# Logic_adapter.net
KiCad netlist of a schematic drawn in Altium Designer
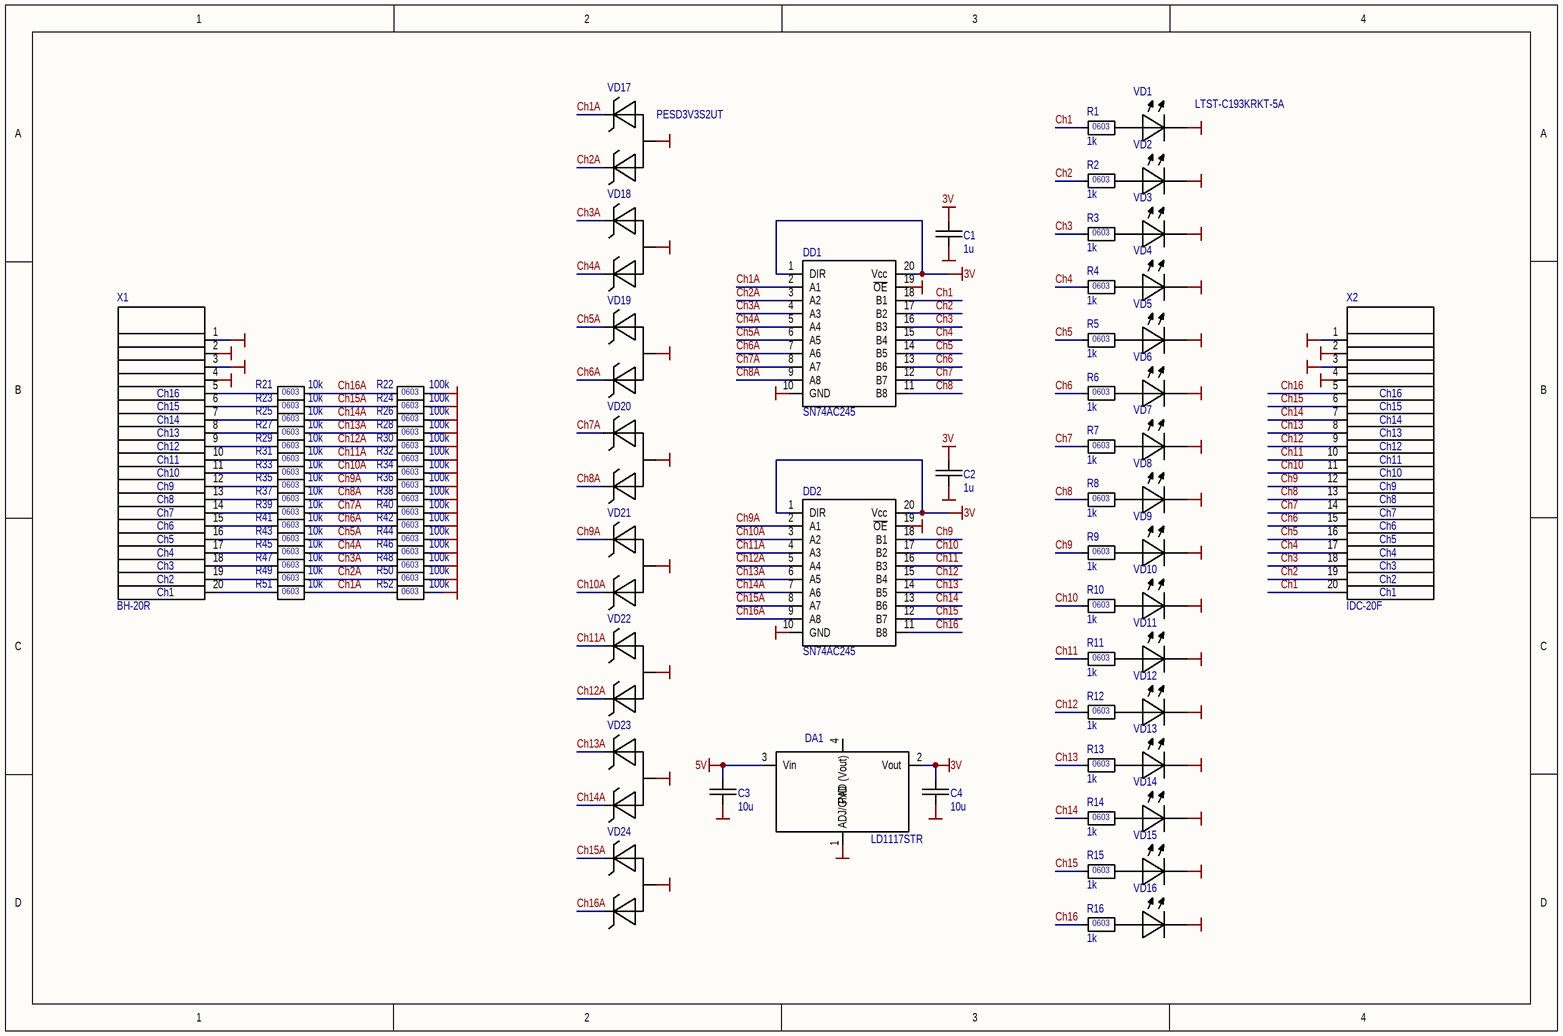
[diagram p0: Logic adapter.SchDoc]

(export (version "E")
  (design (tool "Eeschema 10.0.6"))
  (components
    (comp (ref "C1")
      (value "1u")
      (footprint "C0603")
      (description "General  ceramic capacitor")
      (fields (field (name "PART NUMBER") "GRM185C81A105ME36#") (field (name "VOLTAGE") "10V"))
      (libsource (lib "altium") (part "Capacitor"))
    )
    (comp (ref "C2")
      (value "1u")
      (footprint "C0603")
      (description "General  ceramic capacitor")
      (fields (field (name "PART NUMBER") "GRM185C81A105ME36#") (field (name "VOLTAGE") "10V"))
      (libsource (lib "altium") (part "Capacitor"))
    )
    (comp (ref "C3")
      (value "10u")
      (footprint "C0805")
      (description "General  ceramic capacitor")
      (fields
        (field (name "PART NUMBER") "GRM21BC81A106KE18#")
        (field (name "ALT PART") "C2012X6S1A106K085AC(TDK)")
      )
      (libsource (lib "altium") (part "Capacitor"))
    )
    (comp (ref "C4")
      (value "10u")
      (footprint "C0805")
      (description "General  ceramic capacitor")
      (fields
        (field (name "PART NUMBER") "GRM21BC81A106KE18#")
        (field (name "ALT PART") "C2012X6S1A106K085AC(TDK)")
      )
      (libsource (lib "altium") (part "Capacitor"))
    )
    (comp (ref "DA1")
      (value "~")
      (footprint "ON SEMI SOT-223 ST(318H)")
      (description "LDO ADJ 0.8mA")
      (fields (field (name "PART NUMBER") "LD1117STR") (field (name "LCSC PART #") "C426566"))
      (libsource (lib "altium") (part "LD1117STR"))
    )
    (comp (ref "DD1")
      (value "SN74AC245")
      (footprint "TI-SOIC20 DW")
      (description "Octal bus transceiver")
      (fields (field (name "PART NUMBER") "SN74AC245DW") (field (name "LCSC PART #") "C354145"))
      (libsource (lib "altium") (part "SN74AC245"))
    )
    (comp (ref "DD2")
      (value "SN74AC245")
      (footprint "TI-SOIC20 DW")
      (description "Octal bus transceiver")
      (fields (field (name "PART NUMBER") "SN74AC245DW") (field (name "LCSC PART #") "C354145"))
      (libsource (lib "altium") (part "SN74AC245"))
    )
    (comp (ref "R1")
      (value "1k")
      (footprint "R0603")
      (description "Thick Film Chip Resistor - CR Series")
      (fields (field (name "PART NUMBER") "CR-03FL7----1k") (field (name "ALT PART") "RTT031001FTH (Ralec)"))
      (libsource (lib "altium") (part "Resistor - 0603"))
    )
    (comp (ref "R2")
      (value "1k")
      (footprint "R0603")
      (description "Thick Film Chip Resistor - CR Series")
      (fields (field (name "PART NUMBER") "CR-03FL7----1k") (field (name "ALT PART") "RTT031001FTH (Ralec)"))
      (libsource (lib "altium") (part "Resistor - 0603"))
    )
    (comp (ref "R3")
      (value "1k")
      (footprint "R0603")
      (description "Thick Film Chip Resistor - CR Series")
      (fields (field (name "PART NUMBER") "CR-03FL7----1k") (field (name "ALT PART") "RTT031001FTH (Ralec)"))
      (libsource (lib "altium") (part "Resistor - 0603"))
    )
    (comp (ref "R4")
      (value "1k")
      (footprint "R0603")
      (description "Thick Film Chip Resistor - CR Series")
      (fields (field (name "PART NUMBER") "CR-03FL7----1k") (field (name "ALT PART") "RTT031001FTH (Ralec)"))
      (libsource (lib "altium") (part "Resistor - 0603"))
    )
    (comp (ref "R5")
      (value "1k")
      (footprint "R0603")
      (description "Thick Film Chip Resistor - CR Series")
      (fields (field (name "PART NUMBER") "CR-03FL7----1k") (field (name "ALT PART") "RTT031001FTH (Ralec)"))
      (libsource (lib "altium") (part "Resistor - 0603"))
    )
    (comp (ref "R6")
      (value "1k")
      (footprint "R0603")
      (description "Thick Film Chip Resistor - CR Series")
      (fields (field (name "PART NUMBER") "CR-03FL7----1k") (field (name "ALT PART") "RTT031001FTH (Ralec)"))
      (libsource (lib "altium") (part "Resistor - 0603"))
    )
    (comp (ref "R7")
      (value "1k")
      (footprint "R0603")
      (description "Thick Film Chip Resistor - CR Series")
      (fields (field (name "PART NUMBER") "CR-03FL7----1k") (field (name "ALT PART") "RTT031001FTH (Ralec)"))
      (libsource (lib "altium") (part "Resistor - 0603"))
    )
    (comp (ref "R8")
      (value "1k")
      (footprint "R0603")
      (description "Thick Film Chip Resistor - CR Series")
      (fields (field (name "PART NUMBER") "CR-03FL7----1k") (field (name "ALT PART") "RTT031001FTH (Ralec)"))
      (libsource (lib "altium") (part "Resistor - 0603"))
    )
    (comp (ref "R9")
      (value "1k")
      (footprint "R0603")
      (description "Thick Film Chip Resistor - CR Series")
      (fields (field (name "PART NUMBER") "CR-03FL7----1k") (field (name "ALT PART") "RTT031001FTH (Ralec)"))
      (libsource (lib "altium") (part "Resistor - 0603"))
    )
    (comp (ref "R10")
      (value "1k")
      (footprint "R0603")
      (description "Thick Film Chip Resistor - CR Series")
      (fields (field (name "PART NUMBER") "CR-03FL7----1k") (field (name "ALT PART") "RTT031001FTH (Ralec)"))
      (libsource (lib "altium") (part "Resistor - 0603"))
    )
    (comp (ref "R11")
      (value "1k")
      (footprint "R0603")
      (description "Thick Film Chip Resistor - CR Series")
      (fields (field (name "PART NUMBER") "CR-03FL7----1k") (field (name "ALT PART") "RTT031001FTH (Ralec)"))
      (libsource (lib "altium") (part "Resistor - 0603"))
    )
    (comp (ref "R12")
      (value "1k")
      (footprint "R0603")
      (description "Thick Film Chip Resistor - CR Series")
      (fields (field (name "PART NUMBER") "CR-03FL7----1k") (field (name "ALT PART") "RTT031001FTH (Ralec)"))
      (libsource (lib "altium") (part "Resistor - 0603"))
    )
    (comp (ref "R13")
      (value "1k")
      (footprint "R0603")
      (description "Thick Film Chip Resistor - CR Series")
      (fields (field (name "PART NUMBER") "CR-03FL7----1k") (field (name "ALT PART") "RTT031001FTH (Ralec)"))
      (libsource (lib "altium") (part "Resistor - 0603"))
    )
    (comp (ref "R14")
      (value "1k")
      (footprint "R0603")
      (description "Thick Film Chip Resistor - CR Series")
      (fields (field (name "PART NUMBER") "CR-03FL7----1k") (field (name "ALT PART") "RTT031001FTH (Ralec)"))
      (libsource (lib "altium") (part "Resistor - 0603"))
    )
    (comp (ref "R15")
      (value "1k")
      (footprint "R0603")
      (description "Thick Film Chip Resistor - CR Series")
      (fields (field (name "PART NUMBER") "CR-03FL7----1k") (field (name "ALT PART") "RTT031001FTH (Ralec)"))
      (libsource (lib "altium") (part "Resistor - 0603"))
    )
    (comp (ref "R16")
      (value "1k")
      (footprint "R0603")
      (description "Thick Film Chip Resistor - CR Series")
      (fields (field (name "PART NUMBER") "CR-03FL7----1k") (field (name "ALT PART") "RTT031001FTH (Ralec)"))
      (libsource (lib "altium") (part "Resistor - 0603"))
    )
    (comp (ref "R21")
      (value "10k")
      (footprint "R0603")
      (description "Thick Film Chip Resistor - CR Series")
      (fields (field (name "PART NUMBER") "CR-03FL7---10k") (field (name "ALT PART") "RTT031002FTH (Ralec)"))
      (libsource (lib "altium") (part "Resistor - 0603"))
    )
    (comp (ref "R22")
      (value "100k")
      (footprint "R0603")
      (description "Thick Film Chip Resistor - CR Series")
      (fields (field (name "PART NUMBER") "CR-03FL7--100k") (field (name "ALT PART") "RTT031003FTH (Ralec)"))
      (libsource (lib "altium") (part "Resistor - 0603"))
    )
    (comp (ref "R23")
      (value "10k")
      (footprint "R0603")
      (description "Thick Film Chip Resistor - CR Series")
      (fields (field (name "PART NUMBER") "CR-03FL7---10k") (field (name "ALT PART") "RTT031002FTH (Ralec)"))
      (libsource (lib "altium") (part "Resistor - 0603"))
    )
    (comp (ref "R24")
      (value "100k")
      (footprint "R0603")
      (description "Thick Film Chip Resistor - CR Series")
      (fields (field (name "PART NUMBER") "CR-03FL7--100k") (field (name "ALT PART") "RTT031003FTH (Ralec)"))
      (libsource (lib "altium") (part "Resistor - 0603"))
    )
    (comp (ref "R25")
      (value "10k")
      (footprint "R0603")
      (description "Thick Film Chip Resistor - CR Series")
      (fields (field (name "PART NUMBER") "CR-03FL7---10k") (field (name "ALT PART") "RTT031002FTH (Ralec)"))
      (libsource (lib "altium") (part "Resistor - 0603"))
    )
    (comp (ref "R26")
      (value "100k")
      (footprint "R0603")
      (description "Thick Film Chip Resistor - CR Series")
      (fields (field (name "PART NUMBER") "CR-03FL7--100k") (field (name "ALT PART") "RTT031003FTH (Ralec)"))
      (libsource (lib "altium") (part "Resistor - 0603"))
    )
    (comp (ref "R27")
      (value "10k")
      (footprint "R0603")
      (description "Thick Film Chip Resistor - CR Series")
      (fields (field (name "PART NUMBER") "CR-03FL7---10k") (field (name "ALT PART") "RTT031002FTH (Ralec)"))
      (libsource (lib "altium") (part "Resistor - 0603"))
    )
    (comp (ref "R28")
      (value "100k")
      (footprint "R0603")
      (description "Thick Film Chip Resistor - CR Series")
      (fields (field (name "PART NUMBER") "CR-03FL7--100k") (field (name "ALT PART") "RTT031003FTH (Ralec)"))
      (libsource (lib "altium") (part "Resistor - 0603"))
    )
    (comp (ref "R29")
      (value "10k")
      (footprint "R0603")
      (description "Thick Film Chip Resistor - CR Series")
      (fields (field (name "PART NUMBER") "CR-03FL7---10k") (field (name "ALT PART") "RTT031002FTH (Ralec)"))
      (libsource (lib "altium") (part "Resistor - 0603"))
    )
    (comp (ref "R30")
      (value "100k")
      (footprint "R0603")
      (description "Thick Film Chip Resistor - CR Series")
      (fields (field (name "PART NUMBER") "CR-03FL7--100k") (field (name "ALT PART") "RTT031003FTH (Ralec)"))
      (libsource (lib "altium") (part "Resistor - 0603"))
    )
    (comp (ref "R31")
      (value "10k")
      (footprint "R0603")
      (description "Thick Film Chip Resistor - CR Series")
      (fields (field (name "PART NUMBER") "CR-03FL7---10k") (field (name "ALT PART") "RTT031002FTH (Ralec)"))
      (libsource (lib "altium") (part "Resistor - 0603"))
    )
    (comp (ref "R32")
      (value "100k")
      (footprint "R0603")
      (description "Thick Film Chip Resistor - CR Series")
      (fields (field (name "PART NUMBER") "CR-03FL7--100k") (field (name "ALT PART") "RTT031003FTH (Ralec)"))
      (libsource (lib "altium") (part "Resistor - 0603"))
    )
    (comp (ref "R33")
      (value "10k")
      (footprint "R0603")
      (description "Thick Film Chip Resistor - CR Series")
      (fields (field (name "PART NUMBER") "CR-03FL7---10k") (field (name "ALT PART") "RTT031002FTH (Ralec)"))
      (libsource (lib "altium") (part "Resistor - 0603"))
    )
    (comp (ref "R34")
      (value "100k")
      (footprint "R0603")
      (description "Thick Film Chip Resistor - CR Series")
      (fields (field (name "PART NUMBER") "CR-03FL7--100k") (field (name "ALT PART") "RTT031003FTH (Ralec)"))
      (libsource (lib "altium") (part "Resistor - 0603"))
    )
    (comp (ref "R35")
      (value "10k")
      (footprint "R0603")
      (description "Thick Film Chip Resistor - CR Series")
      (fields (field (name "PART NUMBER") "CR-03FL7---10k") (field (name "ALT PART") "RTT031002FTH (Ralec)"))
      (libsource (lib "altium") (part "Resistor - 0603"))
    )
    (comp (ref "R36")
      (value "100k")
      (footprint "R0603")
      (description "Thick Film Chip Resistor - CR Series")
      (fields (field (name "PART NUMBER") "CR-03FL7--100k") (field (name "ALT PART") "RTT031003FTH (Ralec)"))
      (libsource (lib "altium") (part "Resistor - 0603"))
    )
    (comp (ref "R37")
      (value "10k")
      (footprint "R0603")
      (description "Thick Film Chip Resistor - CR Series")
      (fields (field (name "PART NUMBER") "CR-03FL7---10k") (field (name "ALT PART") "RTT031002FTH (Ralec)"))
      (libsource (lib "altium") (part "Resistor - 0603"))
    )
    (comp (ref "R38")
      (value "100k")
      (footprint "R0603")
      (description "Thick Film Chip Resistor - CR Series")
      (fields (field (name "PART NUMBER") "CR-03FL7--100k") (field (name "ALT PART") "RTT031003FTH (Ralec)"))
      (libsource (lib "altium") (part "Resistor - 0603"))
    )
    (comp (ref "R39")
      (value "10k")
      (footprint "R0603")
      (description "Thick Film Chip Resistor - CR Series")
      (fields (field (name "PART NUMBER") "CR-03FL7---10k") (field (name "ALT PART") "RTT031002FTH (Ralec)"))
      (libsource (lib "altium") (part "Resistor - 0603"))
    )
    (comp (ref "R40")
      (value "100k")
      (footprint "R0603")
      (description "Thick Film Chip Resistor - CR Series")
      (fields (field (name "PART NUMBER") "CR-03FL7--100k") (field (name "ALT PART") "RTT031003FTH (Ralec)"))
      (libsource (lib "altium") (part "Resistor - 0603"))
    )
    (comp (ref "R41")
      (value "10k")
      (footprint "R0603")
      (description "Thick Film Chip Resistor - CR Series")
      (fields (field (name "PART NUMBER") "CR-03FL7---10k") (field (name "ALT PART") "RTT031002FTH (Ralec)"))
      (libsource (lib "altium") (part "Resistor - 0603"))
    )
    (comp (ref "R42")
      (value "100k")
      (footprint "R0603")
      (description "Thick Film Chip Resistor - CR Series")
      (fields (field (name "PART NUMBER") "CR-03FL7--100k") (field (name "ALT PART") "RTT031003FTH (Ralec)"))
      (libsource (lib "altium") (part "Resistor - 0603"))
    )
    (comp (ref "R43")
      (value "10k")
      (footprint "R0603")
      (description "Thick Film Chip Resistor - CR Series")
      (fields (field (name "PART NUMBER") "CR-03FL7---10k") (field (name "ALT PART") "RTT031002FTH (Ralec)"))
      (libsource (lib "altium") (part "Resistor - 0603"))
    )
    (comp (ref "R44")
      (value "100k")
      (footprint "R0603")
      (description "Thick Film Chip Resistor - CR Series")
      (fields (field (name "PART NUMBER") "CR-03FL7--100k") (field (name "ALT PART") "RTT031003FTH (Ralec)"))
      (libsource (lib "altium") (part "Resistor - 0603"))
    )
    (comp (ref "R45")
      (value "10k")
      (footprint "R0603")
      (description "Thick Film Chip Resistor - CR Series")
      (fields (field (name "PART NUMBER") "CR-03FL7---10k") (field (name "ALT PART") "RTT031002FTH (Ralec)"))
      (libsource (lib "altium") (part "Resistor - 0603"))
    )
    (comp (ref "R46")
      (value "100k")
      (footprint "R0603")
      (description "Thick Film Chip Resistor - CR Series")
      (fields (field (name "PART NUMBER") "CR-03FL7--100k") (field (name "ALT PART") "RTT031003FTH (Ralec)"))
      (libsource (lib "altium") (part "Resistor - 0603"))
    )
    (comp (ref "R47")
      (value "10k")
      (footprint "R0603")
      (description "Thick Film Chip Resistor - CR Series")
      (fields (field (name "PART NUMBER") "CR-03FL7---10k") (field (name "ALT PART") "RTT031002FTH (Ralec)"))
      (libsource (lib "altium") (part "Resistor - 0603"))
    )
    (comp (ref "R48")
      (value "100k")
      (footprint "R0603")
      (description "Thick Film Chip Resistor - CR Series")
      (fields (field (name "PART NUMBER") "CR-03FL7--100k") (field (name "ALT PART") "RTT031003FTH (Ralec)"))
      (libsource (lib "altium") (part "Resistor - 0603"))
    )
    (comp (ref "R49")
      (value "10k")
      (footprint "R0603")
      (description "Thick Film Chip Resistor - CR Series")
      (fields (field (name "PART NUMBER") "CR-03FL7---10k") (field (name "ALT PART") "RTT031002FTH (Ralec)"))
      (libsource (lib "altium") (part "Resistor - 0603"))
    )
    (comp (ref "R50")
      (value "100k")
      (footprint "R0603")
      (description "Thick Film Chip Resistor - CR Series")
      (fields (field (name "PART NUMBER") "CR-03FL7--100k") (field (name "ALT PART") "RTT031003FTH (Ralec)"))
      (libsource (lib "altium") (part "Resistor - 0603"))
    )
    (comp (ref "R51")
      (value "10k")
      (footprint "R0603")
      (description "Thick Film Chip Resistor - CR Series")
      (fields (field (name "PART NUMBER") "CR-03FL7---10k") (field (name "ALT PART") "RTT031002FTH (Ralec)"))
      (libsource (lib "altium") (part "Resistor - 0603"))
    )
    (comp (ref "R52")
      (value "100k")
      (footprint "R0603")
      (description "Thick Film Chip Resistor - CR Series")
      (fields (field (name "PART NUMBER") "CR-03FL7--100k") (field (name "ALT PART") "RTT031003FTH (Ralec)"))
      (libsource (lib "altium") (part "Resistor - 0603"))
    )
    (comp (ref "VD1")
      (value "Red")
      (footprint "LTST-C193 RED")
      (description "TopView Single Color Chip LED")
      (fields (field (name "PART NUMBER") "LTST-C193KRKT-5A") (field (name "LCSC PART #") "C157741"))
      (libsource (lib "altium") (part "LED"))
    )
    (comp (ref "VD2")
      (value "Red")
      (footprint "LTST-C193 RED")
      (description "TopView Single Color Chip LED")
      (fields (field (name "PART NUMBER") "LTST-C193KRKT-5A") (field (name "LCSC PART #") "C157741"))
      (libsource (lib "altium") (part "LED"))
    )
    (comp (ref "VD3")
      (value "Red")
      (footprint "LTST-C193 RED")
      (description "TopView Single Color Chip LED")
      (fields (field (name "PART NUMBER") "LTST-C193KRKT-5A") (field (name "LCSC PART #") "C157741"))
      (libsource (lib "altium") (part "LED"))
    )
    (comp (ref "VD4")
      (value "Red")
      (footprint "LTST-C193 RED")
      (description "TopView Single Color Chip LED")
      (fields (field (name "PART NUMBER") "LTST-C193KRKT-5A") (field (name "LCSC PART #") "C157741"))
      (libsource (lib "altium") (part "LED"))
    )
    (comp (ref "VD5")
      (value "Red")
      (footprint "LTST-C193 RED")
      (description "TopView Single Color Chip LED")
      (fields (field (name "PART NUMBER") "LTST-C193KRKT-5A") (field (name "LCSC PART #") "C157741"))
      (libsource (lib "altium") (part "LED"))
    )
    (comp (ref "VD6")
      (value "Red")
      (footprint "LTST-C193 RED")
      (description "TopView Single Color Chip LED")
      (fields (field (name "PART NUMBER") "LTST-C193KRKT-5A") (field (name "LCSC PART #") "C157741"))
      (libsource (lib "altium") (part "LED"))
    )
    (comp (ref "VD7")
      (value "Red")
      (footprint "LTST-C193 RED")
      (description "TopView Single Color Chip LED")
      (fields (field (name "PART NUMBER") "LTST-C193KRKT-5A") (field (name "LCSC PART #") "C157741"))
      (libsource (lib "altium") (part "LED"))
    )
    (comp (ref "VD8")
      (value "Red")
      (footprint "LTST-C193 RED")
      (description "TopView Single Color Chip LED")
      (fields (field (name "PART NUMBER") "LTST-C193KRKT-5A") (field (name "LCSC PART #") "C157741"))
      (libsource (lib "altium") (part "LED"))
    )
    (comp (ref "VD9")
      (value "Red")
      (footprint "LTST-C193 RED")
      (description "TopView Single Color Chip LED")
      (fields (field (name "PART NUMBER") "LTST-C193KRKT-5A") (field (name "LCSC PART #") "C157741"))
      (libsource (lib "altium") (part "LED"))
    )
    (comp (ref "VD10")
      (value "Red")
      (footprint "LTST-C193 RED")
      (description "TopView Single Color Chip LED")
      (fields (field (name "PART NUMBER") "LTST-C193KRKT-5A") (field (name "LCSC PART #") "C157741"))
      (libsource (lib "altium") (part "LED"))
    )
    (comp (ref "VD11")
      (value "Red")
      (footprint "LTST-C193 RED")
      (description "TopView Single Color Chip LED")
      (fields (field (name "PART NUMBER") "LTST-C193KRKT-5A") (field (name "LCSC PART #") "C157741"))
      (libsource (lib "altium") (part "LED"))
    )
    (comp (ref "VD12")
      (value "Red")
      (footprint "LTST-C193 RED")
      (description "TopView Single Color Chip LED")
      (fields (field (name "PART NUMBER") "LTST-C193KRKT-5A") (field (name "LCSC PART #") "C157741"))
      (libsource (lib "altium") (part "LED"))
    )
    (comp (ref "VD13")
      (value "Red")
      (footprint "LTST-C193 RED")
      (description "TopView Single Color Chip LED")
      (fields (field (name "PART NUMBER") "LTST-C193KRKT-5A") (field (name "LCSC PART #") "C157741"))
      (libsource (lib "altium") (part "LED"))
    )
    (comp (ref "VD14")
      (value "Red")
      (footprint "LTST-C193 RED")
      (description "TopView Single Color Chip LED")
      (fields (field (name "PART NUMBER") "LTST-C193KRKT-5A") (field (name "LCSC PART #") "C157741"))
      (libsource (lib "altium") (part "LED"))
    )
    (comp (ref "VD15")
      (value "Red")
      (footprint "LTST-C193 RED")
      (description "TopView Single Color Chip LED")
      (fields (field (name "PART NUMBER") "LTST-C193KRKT-5A") (field (name "LCSC PART #") "C157741"))
      (libsource (lib "altium") (part "LED"))
    )
    (comp (ref "VD16")
      (value "Red")
      (footprint "LTST-C193 RED")
      (description "TopView Single Color Chip LED")
      (fields (field (name "PART NUMBER") "LTST-C193KRKT-5A") (field (name "LCSC PART #") "C157741"))
      (libsource (lib "altium") (part "LED"))
    )
    (comp (ref "VD17")
      (value "PESD3V3S2UT")
      (footprint "NXP-SOT23")
      (description "Double ESD protection diodes")
      (fields (field (name "LCSC PART #") "C84276"))
      (libsource (lib "altium") (part "PESDxS2UT"))
    )
    (comp (ref "VD18")
      (value "PESD3V3S2UT")
      (footprint "NXP-SOT23")
      (description "Double ESD protection diodes")
      (fields (field (name "LCSC PART #") "C84276"))
      (libsource (lib "altium") (part "PESDxS2UT"))
    )
    (comp (ref "VD19")
      (value "PESD3V3S2UT")
      (footprint "NXP-SOT23")
      (description "Double ESD protection diodes")
      (fields (field (name "LCSC PART #") "C84276"))
      (libsource (lib "altium") (part "PESDxS2UT"))
    )
    (comp (ref "VD20")
      (value "PESD3V3S2UT")
      (footprint "NXP-SOT23")
      (description "Double ESD protection diodes")
      (fields (field (name "LCSC PART #") "C84276"))
      (libsource (lib "altium") (part "PESDxS2UT"))
    )
    (comp (ref "VD21")
      (value "PESD3V3S2UT")
      (footprint "NXP-SOT23")
      (description "Double ESD protection diodes")
      (fields (field (name "LCSC PART #") "C84276"))
      (libsource (lib "altium") (part "PESDxS2UT"))
    )
    (comp (ref "VD22")
      (value "PESD3V3S2UT")
      (footprint "NXP-SOT23")
      (description "Double ESD protection diodes")
      (fields (field (name "LCSC PART #") "C84276"))
      (libsource (lib "altium") (part "PESDxS2UT"))
    )
    (comp (ref "VD23")
      (value "PESD3V3S2UT")
      (footprint "NXP-SOT23")
      (description "Double ESD protection diodes")
      (fields (field (name "LCSC PART #") "C84276"))
      (libsource (lib "altium") (part "PESDxS2UT"))
    )
    (comp (ref "VD24")
      (value "PESD3V3S2UT")
      (footprint "NXP-SOT23")
      (description "Double ESD protection diodes")
      (fields (field (name "LCSC PART #") "C84276"))
      (libsource (lib "altium") (part "PESDxS2UT"))
    )
    (comp (ref "X1")
      (value "BH-20R")
      (footprint "BH-20R")
      (description "2.54mm IDC right angle")
      (fields (field (name "LCSC PART #") "C9144"))
      (libsource (lib "altium") (part "Connector-20"))
    )
    (comp (ref "X2")
      (value "IDC-20F")
      (footprint "IDC-20F-EDGE")
      (fields (field (name "LCSC PART #") "C20346"))
      (libsource (lib "altium") (part "Connector-20"))
    )
  )
  (nets
    (net (code "1") (name "/Ch1") (class "Default")
      (node (ref "DD1") (pin "18") (pinfunction "B1_18") (pintype "passive"))
      (node (ref "R1") (pin "1") (pinfunction "1_1") (pintype "passive"))
      (node (ref "X2") (pin "20") (pintype "passive"))
    )
    (net (code "2") (name "/Ch1A") (class "Default")
      (node (ref "DD1") (pin "2") (pinfunction "A1_2") (pintype "passive"))
      (node (ref "R51") (pin "2") (pinfunction "2_2") (pintype "passive"))
      (node (ref "R52") (pin "1") (pinfunction "1_1") (pintype "passive"))
      (node (ref "VD17") (pin "1") (pinfunction "1_1") (pintype "passive"))
    )
    (net (code "3") (name "/Ch2") (class "Default")
      (node (ref "DD1") (pin "17") (pinfunction "B2_17") (pintype "passive"))
      (node (ref "R2") (pin "1") (pinfunction "1_1") (pintype "passive"))
      (node (ref "X2") (pin "19") (pintype "passive"))
    )
    (net (code "4") (name "/Ch2A") (class "Default")
      (node (ref "DD1") (pin "3") (pinfunction "A2_3") (pintype "passive"))
      (node (ref "R49") (pin "2") (pinfunction "2_2") (pintype "passive"))
      (node (ref "R50") (pin "1") (pinfunction "1_1") (pintype "passive"))
      (node (ref "VD17") (pin "2") (pinfunction "2_2") (pintype "passive"))
    )
    (net (code "5") (name "/Ch3") (class "Default")
      (node (ref "DD1") (pin "16") (pinfunction "B3_16") (pintype "passive"))
      (node (ref "R3") (pin "1") (pinfunction "1_1") (pintype "passive"))
      (node (ref "X2") (pin "18") (pintype "passive"))
    )
    (net (code "6") (name "/Ch3A") (class "Default")
      (node (ref "DD1") (pin "4") (pinfunction "A3_4") (pintype "passive"))
      (node (ref "R47") (pin "2") (pinfunction "2_2") (pintype "passive"))
      (node (ref "R48") (pin "1") (pinfunction "1_1") (pintype "passive"))
      (node (ref "VD18") (pin "1") (pinfunction "1_1") (pintype "passive"))
    )
    (net (code "7") (name "/Ch4") (class "Default")
      (node (ref "DD1") (pin "15") (pinfunction "B4_15") (pintype "passive"))
      (node (ref "R4") (pin "1") (pinfunction "1_1") (pintype "passive"))
      (node (ref "X2") (pin "17") (pintype "passive"))
    )
    (net (code "8") (name "/Ch4A") (class "Default")
      (node (ref "DD1") (pin "5") (pinfunction "A4_5") (pintype "passive"))
      (node (ref "R45") (pin "2") (pinfunction "2_2") (pintype "passive"))
      (node (ref "R46") (pin "1") (pinfunction "1_1") (pintype "passive"))
      (node (ref "VD18") (pin "2") (pinfunction "2_2") (pintype "passive"))
    )
    (net (code "9") (name "/Ch5") (class "Default")
      (node (ref "DD1") (pin "14") (pinfunction "B5_14") (pintype "passive"))
      (node (ref "R5") (pin "1") (pinfunction "1_1") (pintype "passive"))
      (node (ref "X2") (pin "16") (pintype "passive"))
    )
    (net (code "10") (name "/Ch5A") (class "Default")
      (node (ref "DD1") (pin "6") (pinfunction "A5_6") (pintype "passive"))
      (node (ref "R43") (pin "2") (pinfunction "2_2") (pintype "passive"))
      (node (ref "R44") (pin "1") (pinfunction "1_1") (pintype "passive"))
      (node (ref "VD19") (pin "1") (pinfunction "1_1") (pintype "passive"))
    )
    (net (code "11") (name "/Ch6") (class "Default")
      (node (ref "DD1") (pin "13") (pinfunction "B6_13") (pintype "passive"))
      (node (ref "R6") (pin "1") (pinfunction "1_1") (pintype "passive"))
      (node (ref "X2") (pin "15") (pintype "passive"))
    )
    (net (code "12") (name "/Ch6A") (class "Default")
      (node (ref "DD1") (pin "7") (pinfunction "A6_7") (pintype "passive"))
      (node (ref "R41") (pin "2") (pinfunction "2_2") (pintype "passive"))
      (node (ref "R42") (pin "1") (pinfunction "1_1") (pintype "passive"))
      (node (ref "VD19") (pin "2") (pinfunction "2_2") (pintype "passive"))
    )
    (net (code "13") (name "/Ch7") (class "Default")
      (node (ref "DD1") (pin "12") (pinfunction "B7_12") (pintype "passive"))
      (node (ref "R7") (pin "1") (pinfunction "1_1") (pintype "passive"))
      (node (ref "X2") (pin "14") (pintype "passive"))
    )
    (net (code "14") (name "/Ch7A") (class "Default")
      (node (ref "DD1") (pin "8") (pinfunction "A7_8") (pintype "passive"))
      (node (ref "R39") (pin "2") (pinfunction "2_2") (pintype "passive"))
      (node (ref "R40") (pin "1") (pinfunction "1_1") (pintype "passive"))
      (node (ref "VD20") (pin "1") (pinfunction "1_1") (pintype "passive"))
    )
    (net (code "15") (name "/Ch8") (class "Default")
      (node (ref "DD1") (pin "11") (pinfunction "B8_11") (pintype "passive"))
      (node (ref "R8") (pin "1") (pinfunction "1_1") (pintype "passive"))
      (node (ref "X2") (pin "13") (pintype "passive"))
    )
    (net (code "16") (name "/Ch8A") (class "Default")
      (node (ref "DD1") (pin "9") (pinfunction "A8_9") (pintype "passive"))
      (node (ref "R37") (pin "2") (pinfunction "2_2") (pintype "passive"))
      (node (ref "R38") (pin "1") (pinfunction "1_1") (pintype "passive"))
      (node (ref "VD20") (pin "2") (pinfunction "2_2") (pintype "passive"))
    )
    (net (code "17") (name "/Ch9") (class "Default")
      (node (ref "DD2") (pin "18") (pinfunction "B1_18") (pintype "passive"))
      (node (ref "R9") (pin "1") (pinfunction "1_1") (pintype "passive"))
      (node (ref "X2") (pin "12") (pintype "passive"))
    )
    (net (code "18") (name "/Ch9A") (class "Default")
      (node (ref "DD2") (pin "2") (pinfunction "A1_2") (pintype "passive"))
      (node (ref "R35") (pin "2") (pinfunction "2_2") (pintype "passive"))
      (node (ref "R36") (pin "1") (pinfunction "1_1") (pintype "passive"))
      (node (ref "VD21") (pin "1") (pinfunction "1_1") (pintype "passive"))
    )
    (net (code "19") (name "/Ch10") (class "Default")
      (node (ref "DD2") (pin "17") (pinfunction "B2_17") (pintype "passive"))
      (node (ref "R10") (pin "1") (pinfunction "1_1") (pintype "passive"))
      (node (ref "X2") (pin "11") (pintype "passive"))
    )
    (net (code "20") (name "/Ch10A") (class "Default")
      (node (ref "DD2") (pin "3") (pinfunction "A2_3") (pintype "passive"))
      (node (ref "R33") (pin "2") (pinfunction "2_2") (pintype "passive"))
      (node (ref "R34") (pin "1") (pinfunction "1_1") (pintype "passive"))
      (node (ref "VD21") (pin "2") (pinfunction "2_2") (pintype "passive"))
    )
    (net (code "21") (name "/Ch11") (class "Default")
      (node (ref "DD2") (pin "16") (pinfunction "B3_16") (pintype "passive"))
      (node (ref "R11") (pin "1") (pinfunction "1_1") (pintype "passive"))
      (node (ref "X2") (pin "10") (pintype "passive"))
    )
    (net (code "22") (name "/Ch11A") (class "Default")
      (node (ref "DD2") (pin "4") (pinfunction "A3_4") (pintype "passive"))
      (node (ref "R31") (pin "2") (pinfunction "2_2") (pintype "passive"))
      (node (ref "R32") (pin "1") (pinfunction "1_1") (pintype "passive"))
      (node (ref "VD22") (pin "1") (pinfunction "1_1") (pintype "passive"))
    )
    (net (code "23") (name "/Ch12") (class "Default")
      (node (ref "DD2") (pin "15") (pinfunction "B4_15") (pintype "passive"))
      (node (ref "R12") (pin "1") (pinfunction "1_1") (pintype "passive"))
      (node (ref "X2") (pin "9") (pintype "passive"))
    )
    (net (code "24") (name "/Ch12A") (class "Default")
      (node (ref "DD2") (pin "5") (pinfunction "A4_5") (pintype "passive"))
      (node (ref "R29") (pin "2") (pinfunction "2_2") (pintype "passive"))
      (node (ref "R30") (pin "1") (pinfunction "1_1") (pintype "passive"))
      (node (ref "VD22") (pin "2") (pinfunction "2_2") (pintype "passive"))
    )
    (net (code "25") (name "/Ch13") (class "Default")
      (node (ref "DD2") (pin "14") (pinfunction "B5_14") (pintype "passive"))
      (node (ref "R13") (pin "1") (pinfunction "1_1") (pintype "passive"))
      (node (ref "X2") (pin "8") (pintype "passive"))
    )
    (net (code "26") (name "/Ch13A") (class "Default")
      (node (ref "DD2") (pin "6") (pinfunction "A5_6") (pintype "passive"))
      (node (ref "R27") (pin "2") (pinfunction "2_2") (pintype "passive"))
      (node (ref "R28") (pin "1") (pinfunction "1_1") (pintype "passive"))
      (node (ref "VD23") (pin "1") (pinfunction "1_1") (pintype "passive"))
    )
    (net (code "27") (name "/Ch14") (class "Default")
      (node (ref "DD2") (pin "13") (pinfunction "B6_13") (pintype "passive"))
      (node (ref "R14") (pin "1") (pinfunction "1_1") (pintype "passive"))
      (node (ref "X2") (pin "7") (pintype "passive"))
    )
    (net (code "28") (name "/Ch14A") (class "Default")
      (node (ref "DD2") (pin "7") (pinfunction "A6_7") (pintype "passive"))
      (node (ref "R25") (pin "2") (pinfunction "2_2") (pintype "passive"))
      (node (ref "R26") (pin "1") (pinfunction "1_1") (pintype "passive"))
      (node (ref "VD23") (pin "2") (pinfunction "2_2") (pintype "passive"))
    )
    (net (code "29") (name "/Ch15") (class "Default")
      (node (ref "DD2") (pin "12") (pinfunction "B7_12") (pintype "passive"))
      (node (ref "R15") (pin "1") (pinfunction "1_1") (pintype "passive"))
      (node (ref "X2") (pin "6") (pintype "passive"))
    )
    (net (code "30") (name "/Ch15A") (class "Default")
      (node (ref "DD2") (pin "8") (pinfunction "A7_8") (pintype "passive"))
      (node (ref "R23") (pin "2") (pinfunction "2_2") (pintype "passive"))
      (node (ref "R24") (pin "1") (pinfunction "1_1") (pintype "passive"))
      (node (ref "VD24") (pin "1") (pinfunction "1_1") (pintype "passive"))
    )
    (net (code "31") (name "/Ch16") (class "Default")
      (node (ref "DD2") (pin "11") (pinfunction "B8_11") (pintype "passive"))
      (node (ref "R16") (pin "1") (pinfunction "1_1") (pintype "passive"))
      (node (ref "X2") (pin "5") (pintype "passive"))
    )
    (net (code "32") (name "/Ch16A") (class "Default")
      (node (ref "DD2") (pin "9") (pinfunction "A8_9") (pintype "passive"))
      (node (ref "R21") (pin "2") (pinfunction "2_2") (pintype "passive"))
      (node (ref "R22") (pin "1") (pinfunction "1_1") (pintype "passive"))
      (node (ref "VD24") (pin "2") (pinfunction "2_2") (pintype "passive"))
    )
    (net (code "33") (name "3V") (class "Default")
      (node (ref "C1") (pin "1") (pinfunction "1_1") (pintype "passive"))
      (node (ref "C2") (pin "1") (pinfunction "1_1") (pintype "passive"))
      (node (ref "C4") (pin "1") (pinfunction "1_1") (pintype "passive"))
      (node (ref "DA1") (pin "2") (pinfunction "Vout_2") (pintype "passive"))
      (node (ref "DD1") (pin "1") (pinfunction "DIR_1") (pintype "passive"))
      (node (ref "DD1") (pin "20") (pinfunction "Vcc_20") (pintype "passive"))
      (node (ref "DD2") (pin "1") (pinfunction "DIR_1") (pintype "passive"))
      (node (ref "DD2") (pin "20") (pinfunction "Vcc_20") (pintype "passive"))
    )
    (net (code "34") (name "5V") (class "Default")
      (node (ref "C3") (pin "1") (pinfunction "1_1") (pintype "passive"))
      (node (ref "DA1") (pin "3") (pinfunction "Vin_3") (pintype "passive"))
    )
    (net (code "35") (name "GND") (class "Default")
      (node (ref "C1") (pin "2") (pinfunction "2_2") (pintype "passive"))
      (node (ref "C2") (pin "2") (pinfunction "2_2") (pintype "passive"))
      (node (ref "C3") (pin "2") (pinfunction "2_2") (pintype "passive"))
      (node (ref "C4") (pin "2") (pinfunction "2_2") (pintype "passive"))
      (node (ref "DA1") (pin "1") (pinfunction "ADJ/GND_1") (pintype "passive"))
      (node (ref "DD1") (pin "10") (pinfunction "GND_10") (pintype "passive"))
      (node (ref "DD1") (pin "19") (pinfunction "~{OE}_19") (pintype "passive"))
      (node (ref "DD2") (pin "10") (pinfunction "GND_10") (pintype "passive"))
      (node (ref "DD2") (pin "19") (pinfunction "~{OE}_19") (pintype "passive"))
      (node (ref "R22") (pin "2") (pinfunction "2_2") (pintype "passive"))
      (node (ref "R24") (pin "2") (pinfunction "2_2") (pintype "passive"))
      (node (ref "R26") (pin "2") (pinfunction "2_2") (pintype "passive"))
      (node (ref "R28") (pin "2") (pinfunction "2_2") (pintype "passive"))
      (node (ref "R30") (pin "2") (pinfunction "2_2") (pintype "passive"))
      (node (ref "R32") (pin "2") (pinfunction "2_2") (pintype "passive"))
      (node (ref "R34") (pin "2") (pinfunction "2_2") (pintype "passive"))
      (node (ref "R36") (pin "2") (pinfunction "2_2") (pintype "passive"))
      (node (ref "R38") (pin "2") (pinfunction "2_2") (pintype "passive"))
      (node (ref "R40") (pin "2") (pinfunction "2_2") (pintype "passive"))
      (node (ref "R42") (pin "2") (pinfunction "2_2") (pintype "passive"))
      (node (ref "R44") (pin "2") (pinfunction "2_2") (pintype "passive"))
      (node (ref "R46") (pin "2") (pinfunction "2_2") (pintype "passive"))
      (node (ref "R48") (pin "2") (pinfunction "2_2") (pintype "passive"))
      (node (ref "R50") (pin "2") (pinfunction "2_2") (pintype "passive"))
      (node (ref "R52") (pin "2") (pinfunction "2_2") (pintype "passive"))
      (node (ref "VD1") (pin "1") (pinfunction "C_1") (pintype "passive"))
      (node (ref "VD10") (pin "1") (pinfunction "C_1") (pintype "passive"))
      (node (ref "VD11") (pin "1") (pinfunction "C_1") (pintype "passive"))
      (node (ref "VD12") (pin "1") (pinfunction "C_1") (pintype "passive"))
      (node (ref "VD13") (pin "1") (pinfunction "C_1") (pintype "passive"))
      (node (ref "VD14") (pin "1") (pinfunction "C_1") (pintype "passive"))
      (node (ref "VD15") (pin "1") (pinfunction "C_1") (pintype "passive"))
      (node (ref "VD16") (pin "1") (pinfunction "C_1") (pintype "passive"))
      (node (ref "VD17") (pin "3") (pinfunction "COM_3") (pintype "passive"))
      (node (ref "VD18") (pin "3") (pinfunction "COM_3") (pintype "passive"))
      (node (ref "VD19") (pin "3") (pinfunction "COM_3") (pintype "passive"))
      (node (ref "VD2") (pin "1") (pinfunction "C_1") (pintype "passive"))
      (node (ref "VD20") (pin "3") (pinfunction "COM_3") (pintype "passive"))
      (node (ref "VD21") (pin "3") (pinfunction "COM_3") (pintype "passive"))
      (node (ref "VD22") (pin "3") (pinfunction "COM_3") (pintype "passive"))
      (node (ref "VD23") (pin "3") (pinfunction "COM_3") (pintype "passive"))
      (node (ref "VD24") (pin "3") (pinfunction "COM_3") (pintype "passive"))
      (node (ref "VD3") (pin "1") (pinfunction "C_1") (pintype "passive"))
      (node (ref "VD4") (pin "1") (pinfunction "C_1") (pintype "passive"))
      (node (ref "VD5") (pin "1") (pinfunction "C_1") (pintype "passive"))
      (node (ref "VD6") (pin "1") (pinfunction "C_1") (pintype "passive"))
      (node (ref "VD7") (pin "1") (pinfunction "C_1") (pintype "passive"))
      (node (ref "VD8") (pin "1") (pinfunction "C_1") (pintype "passive"))
      (node (ref "VD9") (pin "1") (pinfunction "C_1") (pintype "passive"))
      (node (ref "X1") (pin "1") (pintype "passive"))
      (node (ref "X1") (pin "2") (pintype "passive"))
      (node (ref "X1") (pin "3") (pintype "passive"))
      (node (ref "X1") (pin "4") (pintype "passive"))
      (node (ref "X2") (pin "1") (pintype "passive"))
      (node (ref "X2") (pin "2") (pintype "passive"))
      (node (ref "X2") (pin "3") (pintype "passive"))
      (node (ref "X2") (pin "4") (pintype "passive"))
    )
    (net (code "36") (name "Net-(R21-Pad1)") (class "Default")
      (node (ref "R21") (pin "1") (pinfunction "1_1") (pintype "passive"))
      (node (ref "X1") (pin "5") (pintype "passive"))
    )
    (net (code "37") (name "Net-(R23-Pad1)") (class "Default")
      (node (ref "R23") (pin "1") (pinfunction "1_1") (pintype "passive"))
      (node (ref "X1") (pin "6") (pintype "passive"))
    )
    (net (code "38") (name "Net-(R25-Pad1)") (class "Default")
      (node (ref "R25") (pin "1") (pinfunction "1_1") (pintype "passive"))
      (node (ref "X1") (pin "7") (pintype "passive"))
    )
    (net (code "39") (name "Net-(R27-Pad1)") (class "Default")
      (node (ref "R27") (pin "1") (pinfunction "1_1") (pintype "passive"))
      (node (ref "X1") (pin "8") (pintype "passive"))
    )
    (net (code "40") (name "Net-(R29-Pad1)") (class "Default")
      (node (ref "R29") (pin "1") (pinfunction "1_1") (pintype "passive"))
      (node (ref "X1") (pin "9") (pintype "passive"))
    )
    (net (code "41") (name "Net-(R31-Pad1)") (class "Default")
      (node (ref "R31") (pin "1") (pinfunction "1_1") (pintype "passive"))
      (node (ref "X1") (pin "10") (pintype "passive"))
    )
    (net (code "42") (name "Net-(R33-Pad1)") (class "Default")
      (node (ref "R33") (pin "1") (pinfunction "1_1") (pintype "passive"))
      (node (ref "X1") (pin "11") (pintype "passive"))
    )
    (net (code "43") (name "Net-(R35-Pad1)") (class "Default")
      (node (ref "R35") (pin "1") (pinfunction "1_1") (pintype "passive"))
      (node (ref "X1") (pin "12") (pintype "passive"))
    )
    (net (code "44") (name "Net-(R37-Pad1)") (class "Default")
      (node (ref "R37") (pin "1") (pinfunction "1_1") (pintype "passive"))
      (node (ref "X1") (pin "13") (pintype "passive"))
    )
    (net (code "45") (name "Net-(R39-Pad1)") (class "Default")
      (node (ref "R39") (pin "1") (pinfunction "1_1") (pintype "passive"))
      (node (ref "X1") (pin "14") (pintype "passive"))
    )
    (net (code "46") (name "Net-(R41-Pad1)") (class "Default")
      (node (ref "R41") (pin "1") (pinfunction "1_1") (pintype "passive"))
      (node (ref "X1") (pin "15") (pintype "passive"))
    )
    (net (code "47") (name "Net-(R43-Pad1)") (class "Default")
      (node (ref "R43") (pin "1") (pinfunction "1_1") (pintype "passive"))
      (node (ref "X1") (pin "16") (pintype "passive"))
    )
    (net (code "48") (name "Net-(R45-Pad1)") (class "Default")
      (node (ref "R45") (pin "1") (pinfunction "1_1") (pintype "passive"))
      (node (ref "X1") (pin "17") (pintype "passive"))
    )
    (net (code "49") (name "Net-(R47-Pad1)") (class "Default")
      (node (ref "R47") (pin "1") (pinfunction "1_1") (pintype "passive"))
      (node (ref "X1") (pin "18") (pintype "passive"))
    )
    (net (code "50") (name "Net-(R49-Pad1)") (class "Default")
      (node (ref "R49") (pin "1") (pinfunction "1_1") (pintype "passive"))
      (node (ref "X1") (pin "19") (pintype "passive"))
    )
    (net (code "51") (name "Net-(R51-Pad1)") (class "Default")
      (node (ref "R51") (pin "1") (pinfunction "1_1") (pintype "passive"))
      (node (ref "X1") (pin "20") (pintype "passive"))
    )
    (net (code "52") (name "Net-(VD1-A)") (class "Default")
      (node (ref "R1") (pin "2") (pinfunction "2_2") (pintype "passive"))
      (node (ref "VD1") (pin "2") (pinfunction "A_2") (pintype "passive"))
    )
    (net (code "53") (name "Net-(VD2-A)") (class "Default")
      (node (ref "R2") (pin "2") (pinfunction "2_2") (pintype "passive"))
      (node (ref "VD2") (pin "2") (pinfunction "A_2") (pintype "passive"))
    )
    (net (code "54") (name "Net-(VD3-A)") (class "Default")
      (node (ref "R3") (pin "2") (pinfunction "2_2") (pintype "passive"))
      (node (ref "VD3") (pin "2") (pinfunction "A_2") (pintype "passive"))
    )
    (net (code "55") (name "Net-(VD4-A)") (class "Default")
      (node (ref "R4") (pin "2") (pinfunction "2_2") (pintype "passive"))
      (node (ref "VD4") (pin "2") (pinfunction "A_2") (pintype "passive"))
    )
    (net (code "56") (name "Net-(VD5-A)") (class "Default")
      (node (ref "R5") (pin "2") (pinfunction "2_2") (pintype "passive"))
      (node (ref "VD5") (pin "2") (pinfunction "A_2") (pintype "passive"))
    )
    (net (code "57") (name "Net-(VD6-A)") (class "Default")
      (node (ref "R6") (pin "2") (pinfunction "2_2") (pintype "passive"))
      (node (ref "VD6") (pin "2") (pinfunction "A_2") (pintype "passive"))
    )
    (net (code "58") (name "Net-(VD7-A)") (class "Default")
      (node (ref "R7") (pin "2") (pinfunction "2_2") (pintype "passive"))
      (node (ref "VD7") (pin "2") (pinfunction "A_2") (pintype "passive"))
    )
    (net (code "59") (name "Net-(VD8-A)") (class "Default")
      (node (ref "R8") (pin "2") (pinfunction "2_2") (pintype "passive"))
      (node (ref "VD8") (pin "2") (pinfunction "A_2") (pintype "passive"))
    )
    (net (code "60") (name "Net-(VD9-A)") (class "Default")
      (node (ref "R9") (pin "2") (pinfunction "2_2") (pintype "passive"))
      (node (ref "VD9") (pin "2") (pinfunction "A_2") (pintype "passive"))
    )
    (net (code "61") (name "Net-(VD10-A)") (class "Default")
      (node (ref "R10") (pin "2") (pinfunction "2_2") (pintype "passive"))
      (node (ref "VD10") (pin "2") (pinfunction "A_2") (pintype "passive"))
    )
    (net (code "62") (name "Net-(VD11-A)") (class "Default")
      (node (ref "R11") (pin "2") (pinfunction "2_2") (pintype "passive"))
      (node (ref "VD11") (pin "2") (pinfunction "A_2") (pintype "passive"))
    )
    (net (code "63") (name "Net-(VD12-A)") (class "Default")
      (node (ref "R12") (pin "2") (pinfunction "2_2") (pintype "passive"))
      (node (ref "VD12") (pin "2") (pinfunction "A_2") (pintype "passive"))
    )
    (net (code "64") (name "Net-(VD13-A)") (class "Default")
      (node (ref "R13") (pin "2") (pinfunction "2_2") (pintype "passive"))
      (node (ref "VD13") (pin "2") (pinfunction "A_2") (pintype "passive"))
    )
    (net (code "65") (name "Net-(VD14-A)") (class "Default")
      (node (ref "R14") (pin "2") (pinfunction "2_2") (pintype "passive"))
      (node (ref "VD14") (pin "2") (pinfunction "A_2") (pintype "passive"))
    )
    (net (code "66") (name "Net-(VD15-A)") (class "Default")
      (node (ref "R15") (pin "2") (pinfunction "2_2") (pintype "passive"))
      (node (ref "VD15") (pin "2") (pinfunction "A_2") (pintype "passive"))
    )
    (net (code "67") (name "Net-(VD16-A)") (class "Default")
      (node (ref "R16") (pin "2") (pinfunction "2_2") (pintype "passive"))
      (node (ref "VD16") (pin "2") (pinfunction "A_2") (pintype "passive"))
    )
    (net (code "68") (name "unconnected-(DA1-PAD_(Vout)-Pad4)") (class "Default")
      (node (ref "DA1") (pin "4") (pinfunction "PAD_(Vout)_4") (pintype "passive"))
    )
  )
)
